# breakout-r1.net
KiCad netlist of a schematic drawn in EAGLE
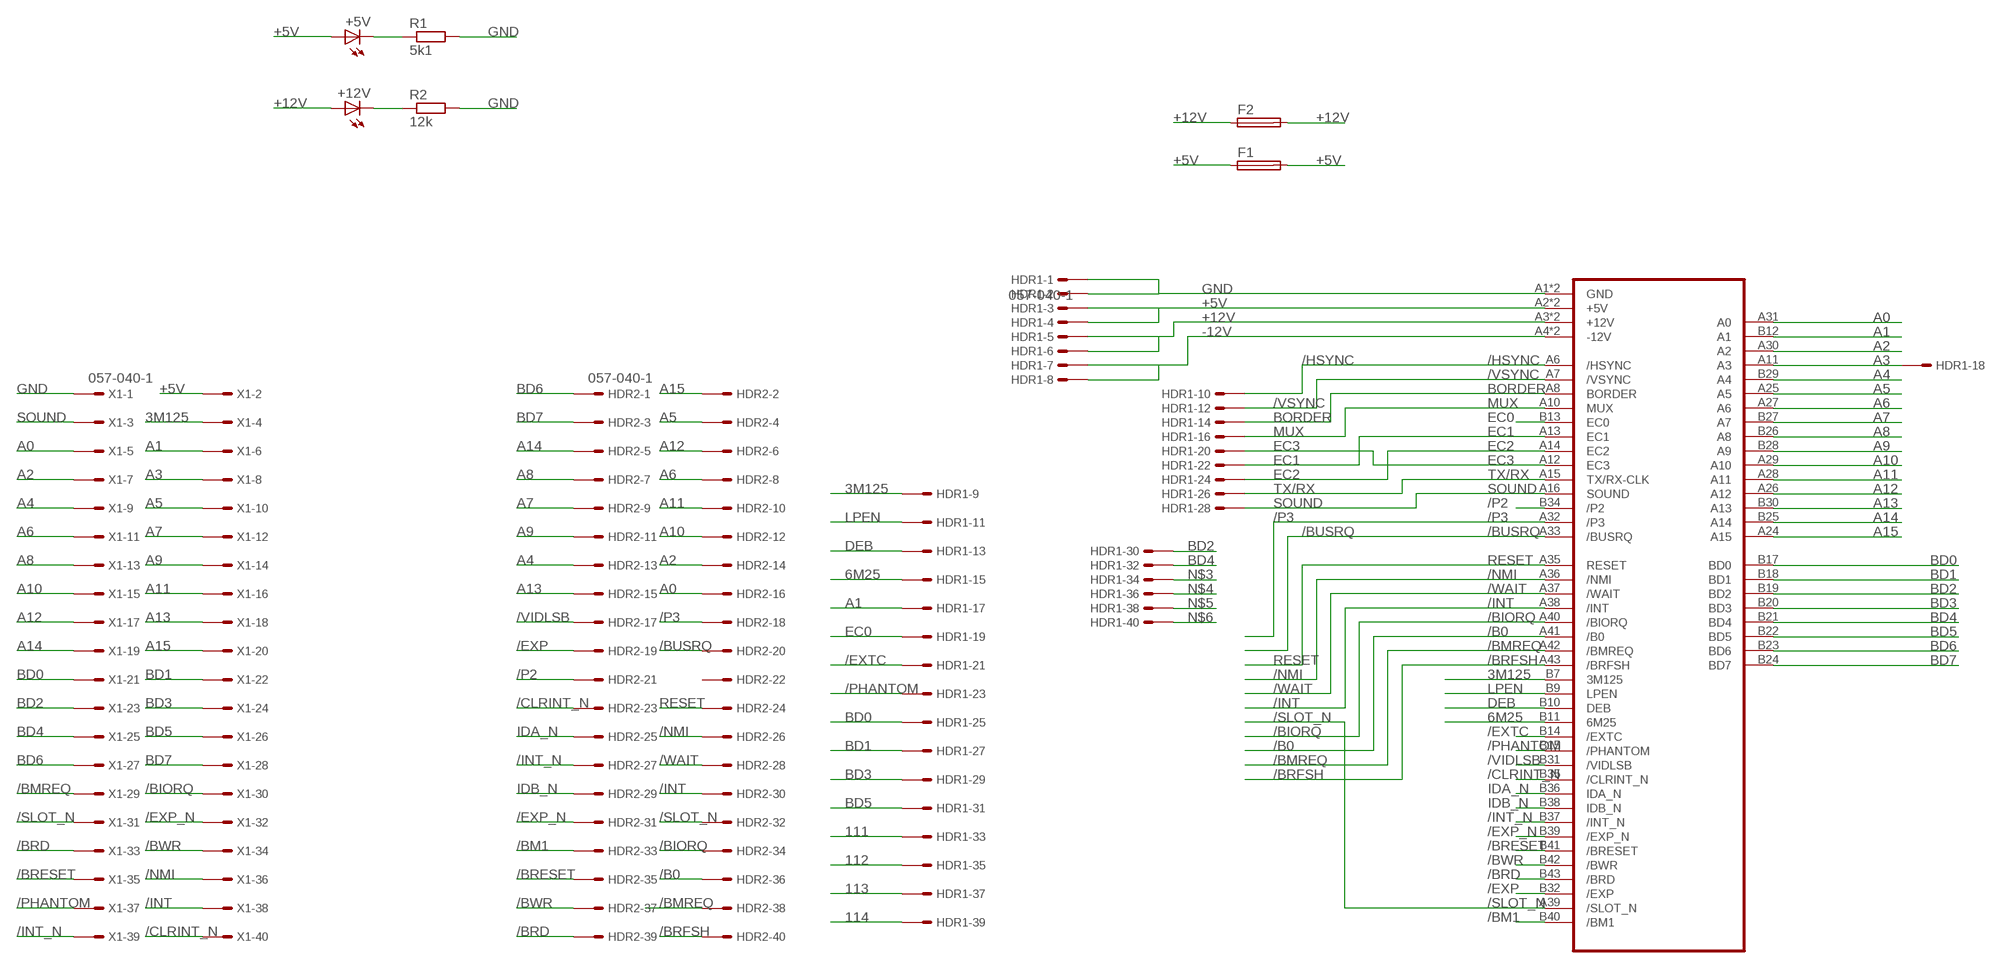
[diagram p0: schematic, sheet 1]

(export (version "E")
  (design (tool "Eeschema 10.0.6"))
  (components
    (comp (ref "+5V")
      (value "LED3MM")
      (footprint "eagle-import:LED3MM")
      (libsource (lib "eagle-import") (part "LED3MM"))
    )
    (comp (ref "+12V")
      (value "LED3MM")
      (footprint "eagle-import:LED3MM")
      (libsource (lib "eagle-import") (part "LED3MM"))
    )
    (comp (ref "F1")
      (value "TE5")
      (footprint "eagle-import:TE5")
      (libsource (lib "eagle-import") (part "TE5"))
    )
    (comp (ref "F2")
      (value "TE5")
      (footprint "eagle-import:TE5")
      (libsource (lib "eagle-import") (part "TE5"))
    )
    (comp (ref "HDR1")
      (value "057-040-1")
      (footprint "eagle-import:057-040-1")
      (libsource (lib "eagle-import") (part "057-040-1"))
    )
    (comp (ref "HDR2")
      (value "057-040-1")
      (footprint "eagle-import:057-040-1")
      (libsource (lib "eagle-import") (part "057-040-1"))
    )
    (comp (ref "R1")
      (value "5k1")
      (footprint "eagle-import:0204_5")
      (libsource (lib "eagle-import") (part "R-EU_0204/5"))
    )
    (comp (ref "R2")
      (value "12k")
      (footprint "eagle-import:0204_5")
      (libsource (lib "eagle-import") (part "R-EU_0204/5"))
    )
    (comp (ref "U$1")
      (value "TVC-EXP-HBA-COMMON")
      (footprint "eagle-import:TVC-EXP-EDGE")
      (libsource (lib "eagle-import") (part "TVC-EXP-HBA-COMMON"))
    )
    (comp (ref "X1")
      (value "057-040-1")
      (footprint "eagle-import:057-040-1")
      (libsource (lib "eagle-import") (part "057-040-1"))
    )
  )
  (nets
    (net (code "1") (name "/+5V") (class "Default")
      (node (ref "+5V") (pin "A") (pinfunction "A_A") (pintype "passive"))
      (node (ref "F1") (pin "1") (pinfunction "1_1") (pintype "passive"))
      (node (ref "F1") (pin "2") (pinfunction "2_2") (pintype "passive"))
      (node (ref "HDR1") (pin "3") (pinfunction "S_3") (pintype "passive"))
      (node (ref "HDR1") (pin "4") (pinfunction "S_4") (pintype "passive"))
      (node (ref "U$1") (pin "A2") (pinfunction "+5V_A2") (pintype "power_in"))
      (node (ref "U$1") (pin "B2") (pinfunction "+5V_B2") (pintype "power_in"))
      (node (ref "X1") (pin "2") (pinfunction "S_2") (pintype "passive"))
    )
    (net (code "2") (name "/+12V") (class "Default")
      (node (ref "+12V") (pin "A") (pinfunction "A_A") (pintype "passive"))
      (node (ref "F2") (pin "1") (pinfunction "1_1") (pintype "passive"))
      (node (ref "F2") (pin "2") (pinfunction "2_2") (pintype "passive"))
      (node (ref "HDR1") (pin "5") (pinfunction "S_5") (pintype "passive"))
      (node (ref "HDR1") (pin "6") (pinfunction "S_6") (pintype "passive"))
      (node (ref "U$1") (pin "A3") (pinfunction "+12V_A3") (pintype "power_in"))
      (node (ref "U$1") (pin "B3") (pinfunction "+12V_B3") (pintype "power_in"))
    )
    (net (code "3") (name "/-12V") (class "Default")
      (node (ref "HDR1") (pin "7") (pinfunction "S_7") (pintype "passive"))
      (node (ref "HDR1") (pin "8") (pinfunction "S_8") (pintype "passive"))
      (node (ref "U$1") (pin "A4") (pinfunction "-12V_A4") (pintype "power_in"))
      (node (ref "U$1") (pin "B4") (pinfunction "-12V_B4") (pintype "power_in"))
    )
    (net (code "4") (name "/3M125") (class "Default")
      (node (ref "HDR1") (pin "9") (pinfunction "S_9") (pintype "passive"))
      (node (ref "U$1") (pin "B7") (pinfunction "3M125_B7") (pintype "bidirectional"))
      (node (ref "X1") (pin "4") (pinfunction "S_4") (pintype "passive"))
    )
    (net (code "5") (name "/6M25") (class "Default")
      (node (ref "HDR1") (pin "15") (pinfunction "S_15") (pintype "passive"))
      (node (ref "U$1") (pin "B11") (pinfunction "6M25_B11") (pintype "bidirectional"))
    )
    (net (code "6") (name "/111") (class "Default")
      (node (ref "HDR1") (pin "33") (pinfunction "S_33") (pintype "passive"))
    )
    (net (code "7") (name "/112") (class "Default")
      (node (ref "HDR1") (pin "35") (pinfunction "S_35") (pintype "passive"))
    )
    (net (code "8") (name "/113") (class "Default")
      (node (ref "HDR1") (pin "37") (pinfunction "S_37") (pintype "passive"))
    )
    (net (code "9") (name "/114") (class "Default")
      (node (ref "HDR1") (pin "39") (pinfunction "S_39") (pintype "passive"))
    )
    (net (code "10") (name "/A0") (class "Default")
      (node (ref "HDR2") (pin "16") (pinfunction "S_16") (pintype "passive"))
      (node (ref "U$1") (pin "A31") (pinfunction "A0_A31") (pintype "bidirectional"))
      (node (ref "X1") (pin "5") (pinfunction "S_5") (pintype "passive"))
    )
    (net (code "11") (name "/A1") (class "Default")
      (node (ref "HDR1") (pin "17") (pinfunction "S_17") (pintype "passive"))
      (node (ref "U$1") (pin "B12") (pinfunction "A1_B12") (pintype "bidirectional"))
      (node (ref "X1") (pin "6") (pinfunction "S_6") (pintype "passive"))
    )
    (net (code "12") (name "/A2") (class "Default")
      (node (ref "HDR2") (pin "14") (pinfunction "S_14") (pintype "passive"))
      (node (ref "U$1") (pin "A30") (pinfunction "A2_A30") (pintype "bidirectional"))
      (node (ref "X1") (pin "7") (pinfunction "S_7") (pintype "passive"))
    )
    (net (code "13") (name "/A3") (class "Default")
      (node (ref "HDR1") (pin "18") (pinfunction "S_18") (pintype "passive"))
      (node (ref "U$1") (pin "A11") (pinfunction "A3_A11") (pintype "bidirectional"))
      (node (ref "X1") (pin "8") (pinfunction "S_8") (pintype "passive"))
    )
    (net (code "14") (name "/A4") (class "Default")
      (node (ref "HDR2") (pin "13") (pinfunction "S_13") (pintype "passive"))
      (node (ref "U$1") (pin "B29") (pinfunction "A4_B29") (pintype "bidirectional"))
      (node (ref "X1") (pin "9") (pinfunction "S_9") (pintype "passive"))
    )
    (net (code "15") (name "/A5") (class "Default")
      (node (ref "HDR2") (pin "4") (pinfunction "S_4") (pintype "passive"))
      (node (ref "U$1") (pin "A25") (pinfunction "A5_A25") (pintype "bidirectional"))
      (node (ref "X1") (pin "10") (pinfunction "S_10") (pintype "passive"))
    )
    (net (code "16") (name "/A6") (class "Default")
      (node (ref "HDR2") (pin "8") (pinfunction "S_8") (pintype "passive"))
      (node (ref "U$1") (pin "A27") (pinfunction "A6_A27") (pintype "bidirectional"))
      (node (ref "X1") (pin "11") (pinfunction "S_11") (pintype "passive"))
    )
    (net (code "17") (name "/A7") (class "Default")
      (node (ref "HDR2") (pin "9") (pinfunction "S_9") (pintype "passive"))
      (node (ref "U$1") (pin "B27") (pinfunction "A7_B27") (pintype "bidirectional"))
      (node (ref "X1") (pin "12") (pinfunction "S_12") (pintype "passive"))
    )
    (net (code "18") (name "/A8") (class "Default")
      (node (ref "HDR2") (pin "7") (pinfunction "S_7") (pintype "passive"))
      (node (ref "U$1") (pin "B26") (pinfunction "A8_B26") (pintype "bidirectional"))
      (node (ref "X1") (pin "13") (pinfunction "S_13") (pintype "passive"))
    )
    (net (code "19") (name "/A9") (class "Default")
      (node (ref "HDR2") (pin "11") (pinfunction "S_11") (pintype "passive"))
      (node (ref "U$1") (pin "B28") (pinfunction "A9_B28") (pintype "bidirectional"))
      (node (ref "X1") (pin "14") (pinfunction "S_14") (pintype "passive"))
    )
    (net (code "20") (name "/A10") (class "Default")
      (node (ref "HDR2") (pin "12") (pinfunction "S_12") (pintype "passive"))
      (node (ref "U$1") (pin "A29") (pinfunction "A10_A29") (pintype "bidirectional"))
      (node (ref "X1") (pin "15") (pinfunction "S_15") (pintype "passive"))
    )
    (net (code "21") (name "/A11") (class "Default")
      (node (ref "HDR2") (pin "10") (pinfunction "S_10") (pintype "passive"))
      (node (ref "U$1") (pin "A28") (pinfunction "A11_A28") (pintype "bidirectional"))
      (node (ref "X1") (pin "16") (pinfunction "S_16") (pintype "passive"))
    )
    (net (code "22") (name "/A12") (class "Default")
      (node (ref "HDR2") (pin "6") (pinfunction "S_6") (pintype "passive"))
      (node (ref "U$1") (pin "A26") (pinfunction "A12_A26") (pintype "bidirectional"))
      (node (ref "X1") (pin "17") (pinfunction "S_17") (pintype "passive"))
    )
    (net (code "23") (name "/A13") (class "Default")
      (node (ref "HDR2") (pin "15") (pinfunction "S_15") (pintype "passive"))
      (node (ref "U$1") (pin "B30") (pinfunction "A13_B30") (pintype "bidirectional"))
      (node (ref "X1") (pin "18") (pinfunction "S_18") (pintype "passive"))
    )
    (net (code "24") (name "/A14") (class "Default")
      (node (ref "HDR2") (pin "5") (pinfunction "S_5") (pintype "passive"))
      (node (ref "U$1") (pin "B25") (pinfunction "A14_B25") (pintype "bidirectional"))
      (node (ref "X1") (pin "19") (pinfunction "S_19") (pintype "passive"))
    )
    (net (code "25") (name "/A15") (class "Default")
      (node (ref "HDR2") (pin "2") (pinfunction "S_2") (pintype "passive"))
      (node (ref "U$1") (pin "A24") (pinfunction "A15_A24") (pintype "bidirectional"))
      (node (ref "X1") (pin "20") (pinfunction "S_20") (pintype "passive"))
    )
    (net (code "26") (name "/BD0") (class "Default")
      (node (ref "HDR1") (pin "25") (pinfunction "S_25") (pintype "passive"))
      (node (ref "U$1") (pin "B17") (pinfunction "BD0_B17") (pintype "bidirectional"))
      (node (ref "X1") (pin "21") (pinfunction "S_21") (pintype "passive"))
    )
    (net (code "27") (name "/BD1") (class "Default")
      (node (ref "HDR1") (pin "27") (pinfunction "S_27") (pintype "passive"))
      (node (ref "U$1") (pin "B18") (pinfunction "BD1_B18") (pintype "bidirectional"))
      (node (ref "X1") (pin "22") (pinfunction "S_22") (pintype "passive"))
    )
    (net (code "28") (name "/BD2") (class "Default")
      (node (ref "HDR1") (pin "30") (pinfunction "S_30") (pintype "passive"))
      (node (ref "U$1") (pin "B19") (pinfunction "BD2_B19") (pintype "bidirectional"))
      (node (ref "X1") (pin "23") (pinfunction "S_23") (pintype "passive"))
    )
    (net (code "29") (name "/BD3") (class "Default")
      (node (ref "HDR1") (pin "29") (pinfunction "S_29") (pintype "passive"))
      (node (ref "U$1") (pin "B20") (pinfunction "BD3_B20") (pintype "bidirectional"))
      (node (ref "X1") (pin "24") (pinfunction "S_24") (pintype "passive"))
    )
    (net (code "30") (name "/BD4") (class "Default")
      (node (ref "HDR1") (pin "32") (pinfunction "S_32") (pintype "passive"))
      (node (ref "U$1") (pin "B21") (pinfunction "BD4_B21") (pintype "bidirectional"))
      (node (ref "X1") (pin "25") (pinfunction "S_25") (pintype "passive"))
    )
    (net (code "31") (name "/BD5") (class "Default")
      (node (ref "HDR1") (pin "31") (pinfunction "S_31") (pintype "passive"))
      (node (ref "U$1") (pin "B22") (pinfunction "BD5_B22") (pintype "bidirectional"))
      (node (ref "X1") (pin "26") (pinfunction "S_26") (pintype "passive"))
    )
    (net (code "32") (name "/BD6") (class "Default")
      (node (ref "HDR2") (pin "1") (pinfunction "S_1") (pintype "passive"))
      (node (ref "U$1") (pin "B23") (pinfunction "BD6_B23") (pintype "bidirectional"))
      (node (ref "X1") (pin "27") (pinfunction "S_27") (pintype "passive"))
    )
    (net (code "33") (name "/BD7") (class "Default")
      (node (ref "HDR2") (pin "3") (pinfunction "S_3") (pintype "passive"))
      (node (ref "U$1") (pin "B24") (pinfunction "BD7_B24") (pintype "bidirectional"))
      (node (ref "X1") (pin "28") (pinfunction "S_28") (pintype "passive"))
    )
    (net (code "34") (name "/BORDER") (class "Default")
      (node (ref "HDR1") (pin "14") (pinfunction "S_14") (pintype "passive"))
      (node (ref "U$1") (pin "A8") (pinfunction "BORDER_A8") (pintype "bidirectional"))
    )
    (net (code "35") (name "/DEB") (class "Default")
      (node (ref "HDR1") (pin "13") (pinfunction "S_13") (pintype "passive"))
      (node (ref "U$1") (pin "B10") (pinfunction "DEB_B10") (pintype "bidirectional"))
    )
    (net (code "36") (name "/EC0") (class "Default")
      (node (ref "HDR1") (pin "19") (pinfunction "S_19") (pintype "passive"))
      (node (ref "U$1") (pin "B13") (pinfunction "EC0_B13") (pintype "bidirectional"))
    )
    (net (code "37") (name "/EC1") (class "Default")
      (node (ref "HDR1") (pin "22") (pinfunction "S_22") (pintype "passive"))
      (node (ref "U$1") (pin "A13") (pinfunction "EC1_A13") (pintype "bidirectional"))
    )
    (net (code "38") (name "/EC2") (class "Default")
      (node (ref "HDR1") (pin "24") (pinfunction "S_24") (pintype "passive"))
      (node (ref "U$1") (pin "A14") (pinfunction "EC2_A14") (pintype "bidirectional"))
    )
    (net (code "39") (name "/EC3") (class "Default")
      (node (ref "HDR1") (pin "20") (pinfunction "S_20") (pintype "passive"))
      (node (ref "U$1") (pin "A12") (pinfunction "EC3_A12") (pintype "bidirectional"))
    )
    (net (code "40") (name "/GND") (class "Default")
      (node (ref "HDR1") (pin "1") (pinfunction "S_1") (pintype "passive"))
      (node (ref "HDR1") (pin "2") (pinfunction "S_2") (pintype "passive"))
      (node (ref "R1") (pin "2") (pinfunction "2_2") (pintype "passive"))
      (node (ref "R2") (pin "2") (pinfunction "2_2") (pintype "passive"))
      (node (ref "U$1") (pin "A1") (pinfunction "GND_A1") (pintype "power_in"))
      (node (ref "U$1") (pin "B1") (pinfunction "GND_B1") (pintype "power_in"))
      (node (ref "X1") (pin "1") (pinfunction "S_1") (pintype "passive"))
    )
    (net (code "41") (name "/IDA_N") (class "Default")
      (node (ref "HDR2") (pin "25") (pinfunction "S_25") (pintype "passive"))
      (node (ref "U$1") (pin "B36") (pinfunction "IDA_N_B36") (pintype "bidirectional"))
    )
    (net (code "42") (name "/IDB_N") (class "Default")
      (node (ref "HDR2") (pin "29") (pinfunction "S_29") (pintype "passive"))
      (node (ref "U$1") (pin "B38") (pinfunction "IDB_N_B38") (pintype "bidirectional"))
    )
    (net (code "43") (name "/LPEN") (class "Default")
      (node (ref "HDR1") (pin "11") (pinfunction "S_11") (pintype "passive"))
      (node (ref "U$1") (pin "B9") (pinfunction "LPEN_B9") (pintype "bidirectional"))
    )
    (net (code "44") (name "/MUX") (class "Default")
      (node (ref "HDR1") (pin "16") (pinfunction "S_16") (pintype "passive"))
      (node (ref "U$1") (pin "A10") (pinfunction "MUX_A10") (pintype "bidirectional"))
    )
    (net (code "45") (name "/N$3") (class "Default")
      (node (ref "HDR1") (pin "34") (pinfunction "S_34") (pintype "passive"))
    )
    (net (code "46") (name "/N$4") (class "Default")
      (node (ref "HDR1") (pin "36") (pinfunction "S_36") (pintype "passive"))
    )
    (net (code "47") (name "/N$5") (class "Default")
      (node (ref "HDR1") (pin "38") (pinfunction "S_38") (pintype "passive"))
    )
    (net (code "48") (name "/N$6") (class "Default")
      (node (ref "HDR1") (pin "40") (pinfunction "S_40") (pintype "passive"))
    )
    (net (code "49") (name "/RESET") (class "Default")
      (node (ref "HDR2") (pin "24") (pinfunction "S_24") (pintype "passive"))
      (node (ref "U$1") (pin "A35") (pinfunction "RESET_A35") (pintype "bidirectional"))
    )
    (net (code "50") (name "/SOUND") (class "Default")
      (node (ref "HDR1") (pin "28") (pinfunction "S_28") (pintype "passive"))
      (node (ref "U$1") (pin "A16") (pinfunction "SOUND_A16") (pintype "bidirectional"))
      (node (ref "X1") (pin "3") (pinfunction "S_3") (pintype "passive"))
    )
    (net (code "51") (name "/TX{slash}RX") (class "Default")
      (node (ref "HDR1") (pin "26") (pinfunction "S_26") (pintype "passive"))
      (node (ref "U$1") (pin "A15") (pinfunction "TX/RX-CLK_A15") (pintype "bidirectional"))
    )
    (net (code "52") (name "/{slash}B0") (class "Default")
      (node (ref "HDR2") (pin "36") (pinfunction "S_36") (pintype "passive"))
      (node (ref "U$1") (pin "A41") (pinfunction "/B0_A41") (pintype "bidirectional"))
    )
    (net (code "53") (name "/{slash}BIORQ") (class "Default")
      (node (ref "HDR2") (pin "34") (pinfunction "S_34") (pintype "passive"))
      (node (ref "U$1") (pin "A40") (pinfunction "/BIORQ_A40") (pintype "output"))
      (node (ref "X1") (pin "30") (pinfunction "S_30") (pintype "passive"))
    )
    (net (code "54") (name "/{slash}BM1") (class "Default")
      (node (ref "HDR2") (pin "33") (pinfunction "S_33") (pintype "passive"))
      (node (ref "U$1") (pin "B40") (pinfunction "/BM1_B40") (pintype "bidirectional"))
    )
    (net (code "55") (name "/{slash}BMREQ") (class "Default")
      (node (ref "HDR2") (pin "38") (pinfunction "S_38") (pintype "passive"))
      (node (ref "U$1") (pin "A42") (pinfunction "/BMREQ_A42") (pintype "output"))
      (node (ref "X1") (pin "29") (pinfunction "S_29") (pintype "passive"))
    )
    (net (code "56") (name "/{slash}BRD") (class "Default")
      (node (ref "HDR2") (pin "39") (pinfunction "S_39") (pintype "passive"))
      (node (ref "U$1") (pin "B43") (pinfunction "/BRD_B43") (pintype "output"))
      (node (ref "X1") (pin "33") (pinfunction "S_33") (pintype "passive"))
    )
    (net (code "57") (name "/{slash}BRESET") (class "Default")
      (node (ref "HDR2") (pin "35") (pinfunction "S_35") (pintype "passive"))
      (node (ref "U$1") (pin "B41") (pinfunction "/BRESET_B41") (pintype "bidirectional"))
      (node (ref "X1") (pin "35") (pinfunction "S_35") (pintype "passive"))
    )
    (net (code "58") (name "/{slash}BRFSH") (class "Default")
      (node (ref "HDR2") (pin "40") (pinfunction "S_40") (pintype "passive"))
      (node (ref "U$1") (pin "A43") (pinfunction "/BRFSH_A43") (pintype "bidirectional"))
    )
    (net (code "59") (name "/{slash}BUSRQ") (class "Default")
      (node (ref "HDR2") (pin "20") (pinfunction "S_20") (pintype "passive"))
      (node (ref "U$1") (pin "A33") (pinfunction "/BUSRQ_A33") (pintype "bidirectional"))
    )
    (net (code "60") (name "/{slash}BWR") (class "Default")
      (node (ref "HDR2") (pin "37") (pinfunction "S_37") (pintype "passive"))
      (node (ref "U$1") (pin "B42") (pinfunction "/BWR_B42") (pintype "output"))
      (node (ref "X1") (pin "34") (pinfunction "S_34") (pintype "passive"))
    )
    (net (code "61") (name "/{slash}CLRINT_N") (class "Default")
      (node (ref "HDR2") (pin "23") (pinfunction "S_23") (pintype "passive"))
      (node (ref "U$1") (pin "B35") (pinfunction "/CLRINT_N_B35") (pintype "bidirectional"))
      (node (ref "X1") (pin "40") (pinfunction "S_40") (pintype "passive"))
    )
    (net (code "62") (name "/{slash}EXP") (class "Default")
      (node (ref "HDR2") (pin "19") (pinfunction "S_19") (pintype "passive"))
      (node (ref "U$1") (pin "B32") (pinfunction "/EXP_B32") (pintype "bidirectional"))
    )
    (net (code "63") (name "/{slash}EXP_N") (class "Default")
      (node (ref "HDR2") (pin "31") (pinfunction "S_31") (pintype "passive"))
      (node (ref "U$1") (pin "B39") (pinfunction "/EXP_N_B39") (pintype "bidirectional"))
      (node (ref "X1") (pin "32") (pinfunction "S_32") (pintype "passive"))
    )
    (net (code "64") (name "/{slash}EXTC") (class "Default")
      (node (ref "HDR1") (pin "21") (pinfunction "S_21") (pintype "passive"))
      (node (ref "U$1") (pin "B14") (pinfunction "/EXTC_B14") (pintype "bidirectional"))
    )
    (net (code "65") (name "/{slash}HSYNC") (class "Default")
      (node (ref "HDR1") (pin "10") (pinfunction "S_10") (pintype "passive"))
      (node (ref "U$1") (pin "A6") (pinfunction "/HSYNC_A6") (pintype "bidirectional"))
    )
    (net (code "66") (name "/{slash}INT") (class "Default")
      (node (ref "HDR2") (pin "30") (pinfunction "S_30") (pintype "passive"))
      (node (ref "U$1") (pin "A38") (pinfunction "/INT_A38") (pintype "bidirectional"))
      (node (ref "X1") (pin "38") (pinfunction "S_38") (pintype "passive"))
    )
    (net (code "67") (name "/{slash}INT_N") (class "Default")
      (node (ref "HDR2") (pin "27") (pinfunction "S_27") (pintype "passive"))
      (node (ref "U$1") (pin "B37") (pinfunction "/INT_N_B37") (pintype "bidirectional"))
      (node (ref "X1") (pin "39") (pinfunction "S_39") (pintype "passive"))
    )
    (net (code "68") (name "/{slash}NMI") (class "Default")
      (node (ref "HDR2") (pin "26") (pinfunction "S_26") (pintype "passive"))
      (node (ref "U$1") (pin "A36") (pinfunction "/NMI_A36") (pintype "bidirectional"))
      (node (ref "X1") (pin "36") (pinfunction "S_36") (pintype "passive"))
    )
    (net (code "69") (name "/{slash}P2") (class "Default")
      (node (ref "HDR2") (pin "21") (pinfunction "S_21") (pintype "passive"))
      (node (ref "U$1") (pin "B34") (pinfunction "/P2_B34") (pintype "bidirectional"))
    )
    (net (code "70") (name "/{slash}P3") (class "Default")
      (node (ref "HDR2") (pin "18") (pinfunction "S_18") (pintype "passive"))
      (node (ref "U$1") (pin "A32") (pinfunction "/P3_A32") (pintype "bidirectional"))
    )
    (net (code "71") (name "/{slash}PHANTOM") (class "Default")
      (node (ref "HDR1") (pin "23") (pinfunction "S_23") (pintype "passive"))
      (node (ref "U$1") (pin "B15") (pinfunction "/PHANTOM_B15") (pintype "bidirectional"))
      (node (ref "X1") (pin "37") (pinfunction "S_37") (pintype "passive"))
    )
    (net (code "72") (name "/{slash}SLOT_N") (class "Default")
      (node (ref "HDR2") (pin "32") (pinfunction "S_32") (pintype "passive"))
      (node (ref "U$1") (pin "A39") (pinfunction "/SLOT_N_A39") (pintype "input"))
      (node (ref "X1") (pin "31") (pinfunction "S_31") (pintype "passive"))
    )
    (net (code "73") (name "/{slash}VIDLSB") (class "Default")
      (node (ref "HDR2") (pin "17") (pinfunction "S_17") (pintype "passive"))
      (node (ref "U$1") (pin "B31") (pinfunction "/VIDLSB_B31") (pintype "bidirectional"))
    )
    (net (code "74") (name "/{slash}VSYNC") (class "Default")
      (node (ref "HDR1") (pin "12") (pinfunction "S_12") (pintype "passive"))
      (node (ref "U$1") (pin "A7") (pinfunction "/VSYNC_A7") (pintype "bidirectional"))
    )
    (net (code "75") (name "/{slash}WAIT") (class "Default")
      (node (ref "HDR2") (pin "28") (pinfunction "S_28") (pintype "passive"))
      (node (ref "U$1") (pin "A37") (pinfunction "/WAIT_A37") (pintype "bidirectional"))
    )
    (net (code "76") (name "Net-(+5V-C)") (class "Default")
      (node (ref "+5V") (pin "K") (pinfunction "C_K") (pintype "passive"))
      (node (ref "R1") (pin "1") (pinfunction "1_1") (pintype "passive"))
    )
    (net (code "77") (name "Net-(+12V-C)") (class "Default")
      (node (ref "+12V") (pin "K") (pinfunction "C_K") (pintype "passive"))
      (node (ref "R2") (pin "1") (pinfunction "1_1") (pintype "passive"))
    )
    (net (code "78") (name "unconnected-(HDR2O-S-Pad22)") (class "Default")
      (node (ref "HDR2") (pin "22") (pinfunction "S_22") (pintype "passive"))
    )
  )
)
